# SOM.net
KiCad netlist of a schematic drawn in Altium Designer
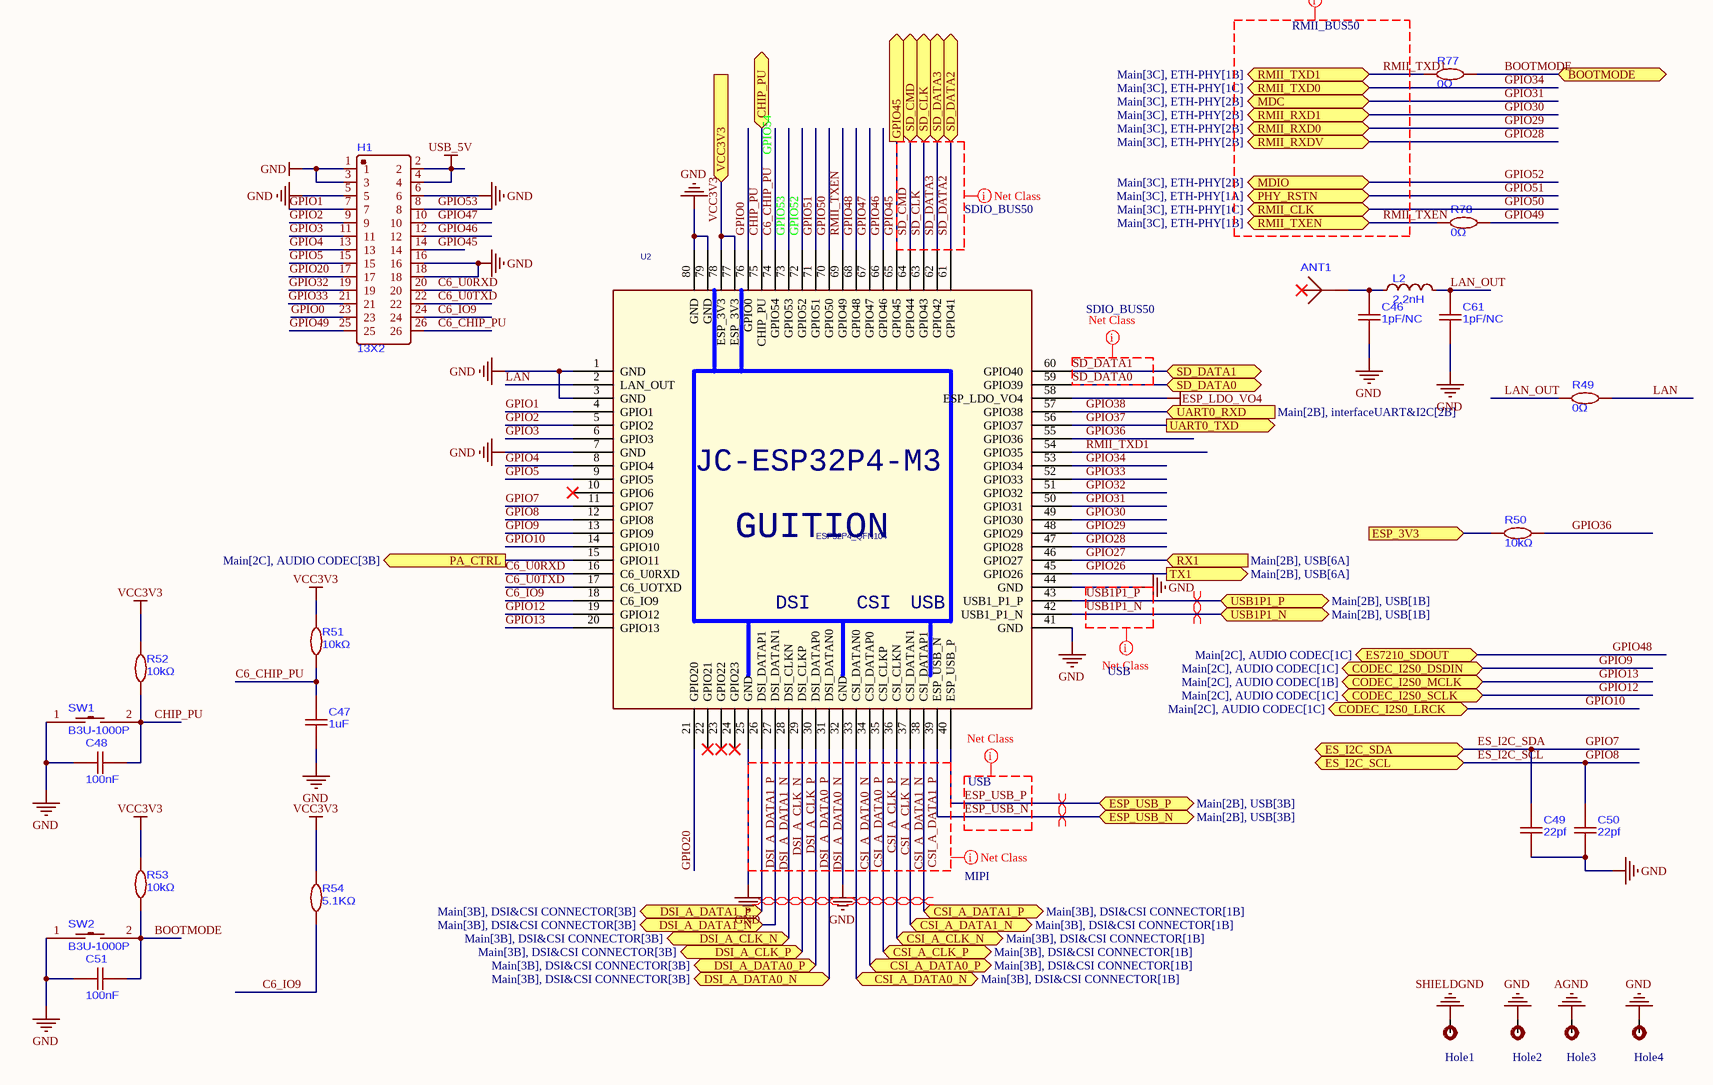
[diagram p0: SOM.SchDoc]

(export (version "E")
  (design (tool "Eeschema 10.0.6"))
  (components
    (comp (ref "ANT1")
      (value "RF ANT 2450MHz CERAMIC SMD")
      (footprint "ANT-SMD-2_L3.2-W1.6-C504002")
      (description "Ceramic Antenna 5.19dBi 100MHz 2.45GHz 1206 RF Antennas RoHS")
      (libsource (lib "Schlib2") (part "kinghelm KH-3216-A35"))
    )
    (comp (ref "C46")
      (value "1pF/NC")
      (footprint "C0402")
      (description "50V 1pF C0G 0603 Ceramic Capacitors RoHS")
      (libsource (lib "Schlib2") (part "FCC0603N1R0C500CT"))
    )
    (comp (ref "C47")
      (value "1uF")
      (footprint "C0603")
      (description "25V 1uF X7R ±10% 0603 Ceramic Capacitors ROHS")
      (libsource (lib "Schlib2") (part "CL10B105KA8NNNC"))
    )
    (comp (ref "C48")
      (value "100nF")
      (footprint "C0603")
      (description "50V 100nF X7R ±10% 0603 Ceramic Capacitors ROHS")
      (libsource (lib "Schlib2") (part "CC0603KRX7R9BB104"))
    )
    (comp (ref "C49")
      (value "22pf")
      (footprint "C0603")
      (description "50V 22pF C0G ±5% 0603 Ceramic Capacitors RoHS")
      (libsource (lib "Schlib2") (part "CL10C220JB8NNNC"))
    )
    (comp (ref "C50")
      (value "22pf")
      (footprint "C0603")
      (description "50V 22pF C0G ±5% 0603 Ceramic Capacitors RoHS")
      (libsource (lib "Schlib2") (part "CL10C220JB8NNNC"))
    )
    (comp (ref "C51")
      (value "100nF")
      (footprint "C0603")
      (description "50V 100nF X7R ±10% 0603 Ceramic Capacitors ROHS")
      (libsource (lib "Schlib2") (part "CC0603KRX7R9BB104"))
    )
    (comp (ref "C61")
      (value "1pF/NC")
      (footprint "C0402")
      (description "50V 1pF C0G 0603 Ceramic Capacitors RoHS")
      (libsource (lib "Schlib2") (part "FCC0603N1R0C500CT"))
    )
    (comp (ref "H1")
      (value "13X2")
      (footprint "HDR-TH_26P-P2.54-V-M-R2-C13-S2.54")
      (libsource (lib "Schlib2") (part "HX PZ2.54-2X13P ZZ"))
    )
    (comp (ref "Hole1")
      (value "Pad Big")
      (footprint "Screw 3.0")
      (libsource (lib "Schlib2") (part "Pad_Big"))
    )
    (comp (ref "Hole2")
      (value "Pad Big")
      (footprint "Screw 3.0")
      (libsource (lib "Schlib2") (part "Pad_Big"))
    )
    (comp (ref "Hole3")
      (value "Pad Big")
      (footprint "Screw 3.0")
      (libsource (lib "Schlib2") (part "Pad_Big"))
    )
    (comp (ref "Hole4")
      (value "Pad Big")
      (footprint "Screw 3.0")
      (libsource (lib "Schlib2") (part "Pad_Big"))
    )
    (comp (ref "L2")
      (value "2.2nH")
      (footprint "C0402")
      (description "700mA 2.2nH ±5% Wirewound Chip Inductor 80mΩ 0603 Fixed Inductors RoHS")
      (libsource (lib "Schlib2") (part "MQG06HF2N2JT7"))
    )
    (comp (ref "R49")
      (value "0Ω")
      (footprint "R0402")
      (description "100mW 0Ω 75V Thick Film Resistor ±5% 0603 Chip Resistor - Surface Mount RoHS")
      (libsource (lib "Schlib2") (part "RC0603JR-070RL"))
    )
    (comp (ref "R50")
      (value "10kΩ")
      (footprint "R0603")
      (description "100mW 10kΩ 75V ±100ppm/℃ Thick Film Resistor ±1% 0603 Chip Resistor - Surface Mount ROHS")
      (libsource (lib "Schlib2") (part "RC0603FR-0710KL"))
    )
    (comp (ref "R51")
      (value "10kΩ")
      (footprint "R0603")
      (description "100mW 10kΩ 75V ±100ppm/℃ Thick Film Resistor ±1% 0603 Chip Resistor - Surface Mount ROHS")
      (libsource (lib "Schlib2") (part "RC0603FR-0710KL"))
    )
    (comp (ref "R52")
      (value "10kΩ")
      (footprint "R0603")
      (description "100mW 10kΩ 75V ±100ppm/℃ Thick Film Resistor ±1% 0603 Chip Resistor - Surface Mount ROHS")
      (libsource (lib "Schlib2") (part "RC0603FR-0710KL"))
    )
    (comp (ref "R53")
      (value "10kΩ")
      (footprint "R0603")
      (description "100mW 10kΩ 75V ±100ppm/℃ Thick Film Resistor ±1% 0603 Chip Resistor - Surface Mount ROHS")
      (libsource (lib "Schlib2") (part "RC0603FR-0710KL"))
    )
    (comp (ref "R54")
      (value "5.1KΩ")
      (footprint "R0603")
      (description "100mW 5.1kΩ 75V ±100ppm/℃ Thick Film Resistor ±1% 0603 Chip Resistor - Surface Mount RoHS")
      (libsource (lib "Schlib2") (part "FRC0603F5101TS"))
    )
    (comp (ref "R77")
      (value "0Ω")
      (footprint "R0402")
      (description "100mW 0Ω 75V Thick Film Resistor ±5% 0603 Chip Resistor - Surface Mount RoHS")
      (libsource (lib "Schlib2") (part "RC0603JR-070RL"))
    )
    (comp (ref "R78")
      (value "0Ω")
      (footprint "R0402")
      (description "100mW 0Ω 75V Thick Film Resistor ±5% 0603 Chip Resistor - Surface Mount RoHS")
      (libsource (lib "Schlib2") (part "RC0603JR-070RL"))
    )
    (comp (ref "SW1")
      (value "B3U-1000P")
      (footprint "KEY-SMD_B3U-1000PM")
      (description "12V 2.5mm Round Button 3mm SPST 50mA SMD,3x2.5mm Tactile Switches ROHS")
      (libsource (lib "Schlib2") (part "B3U-1000P"))
    )
    (comp (ref "SW2")
      (value "B3U-1000P")
      (footprint "KEY-SMD_B3U-1000PM")
      (description "12V 2.5mm Round Button 3mm SPST 50mA SMD,3x2.5mm Tactile Switches ROHS")
      (libsource (lib "Schlib2") (part "B3U-1000P"))
    )
    (comp (ref "U2")
      (value "ESP32P4_QFN104")
      (footprint "JC-ESP32P4-M3_V0.2")
      (libsource (lib "Schlib2") (part "JC-ESP32P4-M3"))
    )
  )
  (nets
    (net (code "1") (name "/BOOTMODE") (class "Default")
      (node (ref "C51") (pin "1") (pinfunction "1_1") (pintype "passive"))
      (node (ref "R53") (pin "1") (pinfunction "1_1") (pintype "passive"))
      (node (ref "R77") (pin "2") (pinfunction "2_2") (pintype "passive"))
      (node (ref "SW2") (pin "2") (pinfunction "2_2") (pintype "passive"))
    )
    (net (code "2") (name "/C6_CHIP_PU") (class "Default")
      (node (ref "C47") (pin "2") (pinfunction "2_2") (pintype "passive"))
      (node (ref "H1") (pin "26") (pinfunction "26_26") (pintype "passive"))
      (node (ref "R51") (pin "1") (pinfunction "1_1") (pintype "passive"))
      (node (ref "U2") (pin "74") (pinfunction "GPIO54_74") (pintype "passive"))
    )
    (net (code "3") (name "/C6_IO9") (class "Default")
      (node (ref "H1") (pin "24") (pinfunction "24_24") (pintype "passive"))
      (node (ref "R54") (pin "1") (pinfunction "1_1") (pintype "passive"))
      (node (ref "U2") (pin "18") (pinfunction "C6_IO9_18") (pintype "passive"))
    )
    (net (code "4") (name "/C6_U0RXD") (class "Default")
      (node (ref "H1") (pin "20") (pinfunction "20_20") (pintype "passive"))
      (node (ref "U2") (pin "16") (pinfunction "C6_U0RXD_16") (pintype "passive"))
    )
    (net (code "5") (name "/C6_U0TXD") (class "Default")
      (node (ref "H1") (pin "22") (pinfunction "22_22") (pintype "passive"))
      (node (ref "U2") (pin "17") (pinfunction "C6_UOTXD_17") (pintype "passive"))
    )
    (net (code "6") (name "/CHIP_PU") (class "Default")
      (node (ref "C48") (pin "1") (pinfunction "1_1") (pintype "passive"))
      (node (ref "R52") (pin "1") (pinfunction "1_1") (pintype "passive"))
      (node (ref "SW1") (pin "2") (pinfunction "2_2") (pintype "passive"))
      (node (ref "U2") (pin "75") (pinfunction "CHIP_PU_75") (pintype "passive"))
    )
    (net (code "7") (name "/CSI_A_CLK_N") (class "Default")
      (node (ref "U2") (pin "36") (pinfunction "CSI_CLKN_36") (pintype "passive"))
    )
    (net (code "8") (name "/CSI_A_CLK_P") (class "Default")
      (node (ref "U2") (pin "35") (pinfunction "CSI_CLKP_35") (pintype "passive"))
    )
    (net (code "9") (name "/CSI_A_DATA0_N") (class "Default")
      (node (ref "U2") (pin "33") (pinfunction "CSI_DATAN0_33") (pintype "passive"))
    )
    (net (code "10") (name "/CSI_A_DATA0_P") (class "Default")
      (node (ref "U2") (pin "34") (pinfunction "CSI_DATAP0_34") (pintype "passive"))
    )
    (net (code "11") (name "/CSI_A_DATA1_N") (class "Default")
      (node (ref "U2") (pin "37") (pinfunction "CSI_DATAN1_37") (pintype "passive"))
    )
    (net (code "12") (name "/CSI_A_DATA1_P") (class "Default")
      (node (ref "U2") (pin "38") (pinfunction "CSI_DATAP1_38") (pintype "passive"))
    )
    (net (code "13") (name "/DSI_A_CLK_N") (class "Default")
      (node (ref "U2") (pin "28") (pinfunction "DSI_CLKN_28") (pintype "passive"))
    )
    (net (code "14") (name "/DSI_A_CLK_P") (class "Default")
      (node (ref "U2") (pin "29") (pinfunction "DSI_CLKP_29") (pintype "passive"))
    )
    (net (code "15") (name "/DSI_A_DATA0_N") (class "Default")
      (node (ref "U2") (pin "31") (pinfunction "DSI_DATAN0_31") (pintype "passive"))
    )
    (net (code "16") (name "/DSI_A_DATA0_P") (class "Default")
      (node (ref "U2") (pin "30") (pinfunction "DSI_DATAP0_30") (pintype "passive"))
    )
    (net (code "17") (name "/DSI_A_DATA1_N") (class "Default")
      (node (ref "U2") (pin "27") (pinfunction "DSI_DATAN1_27") (pintype "passive"))
    )
    (net (code "18") (name "/DSI_A_DATA1_P") (class "Default")
      (node (ref "U2") (pin "26") (pinfunction "DSI_DATAP1_26") (pintype "passive"))
    )
    (net (code "19") (name "/ESP_3V3") (class "Default")
      (node (ref "R50") (pin "1") (pinfunction "1_1") (pintype "passive"))
    )
    (net (code "20") (name "/ESP_USB_N") (class "Default")
      (node (ref "U2") (pin "39") (pinfunction "ESP_USB_N_39") (pintype "passive"))
    )
    (net (code "21") (name "/ESP_USB_P") (class "Default")
      (node (ref "U2") (pin "40") (pinfunction "ESP_USB_P_40") (pintype "passive"))
    )
    (net (code "22") (name "/ES_I2C_SCL") (class "Default")
      (node (ref "C50") (pin "2") (pinfunction "2_2") (pintype "passive"))
      (node (ref "U2") (pin "12") (pinfunction "GPIO8_12") (pintype "passive"))
    )
    (net (code "23") (name "/ES_I2C_SDA") (class "Default")
      (node (ref "C49") (pin "2") (pinfunction "2_2") (pintype "passive"))
      (node (ref "U2") (pin "11") (pinfunction "GPIO7_11") (pintype "passive"))
    )
    (net (code "24") (name "/GPIO0") (class "Default")
      (node (ref "H1") (pin "23") (pinfunction "23_23") (pintype "passive"))
      (node (ref "U2") (pin "76") (pinfunction "GPIO0_76") (pintype "passive"))
    )
    (net (code "25") (name "/GPIO1") (class "Default")
      (node (ref "H1") (pin "7") (pinfunction "7_7") (pintype "passive"))
      (node (ref "U2") (pin "4") (pinfunction "GPIO1_4") (pintype "passive"))
    )
    (net (code "26") (name "/GPIO2") (class "Default")
      (node (ref "H1") (pin "9") (pinfunction "9_9") (pintype "passive"))
      (node (ref "U2") (pin "5") (pinfunction "GPIO2_5") (pintype "passive"))
    )
    (net (code "27") (name "/GPIO3") (class "Default")
      (node (ref "H1") (pin "11") (pinfunction "11_11") (pintype "passive"))
      (node (ref "U2") (pin "6") (pinfunction "GPIO3_6") (pintype "passive"))
    )
    (net (code "28") (name "/GPIO4") (class "Default")
      (node (ref "H1") (pin "13") (pinfunction "13_13") (pintype "passive"))
      (node (ref "U2") (pin "8") (pinfunction "GPIO4_8") (pintype "passive"))
    )
    (net (code "29") (name "/GPIO5") (class "Default")
      (node (ref "H1") (pin "15") (pinfunction "15_15") (pintype "passive"))
      (node (ref "U2") (pin "9") (pinfunction "GPIO5_9") (pintype "passive"))
    )
    (net (code "30") (name "/GPIO9") (class "Default")
      (node (ref "U2") (pin "13") (pinfunction "GPIO9_13") (pintype "passive"))
    )
    (net (code "31") (name "/GPIO10") (class "Default")
      (node (ref "U2") (pin "14") (pinfunction "GPIO10_14") (pintype "passive"))
    )
    (net (code "32") (name "/GPIO12") (class "Default")
      (node (ref "U2") (pin "19") (pinfunction "GPIO12_19") (pintype "passive"))
    )
    (net (code "33") (name "/GPIO13") (class "Default")
      (node (ref "U2") (pin "20") (pinfunction "GPIO13_20") (pintype "passive"))
    )
    (net (code "34") (name "/GPIO20") (class "Default")
      (node (ref "H1") (pin "17") (pinfunction "17_17") (pintype "passive"))
      (node (ref "U2") (pin "21") (pinfunction "GPIO20_21") (pintype "passive"))
    )
    (net (code "35") (name "/GPIO26") (class "Default")
      (node (ref "U2") (pin "45") (pinfunction "GPIO26_45") (pintype "passive"))
    )
    (net (code "36") (name "/GPIO27") (class "Default")
      (node (ref "U2") (pin "46") (pinfunction "GPIO27_46") (pintype "passive"))
    )
    (net (code "37") (name "/GPIO28") (class "Default")
      (node (ref "U2") (pin "47") (pinfunction "GPIO28_47") (pintype "passive"))
    )
    (net (code "38") (name "/GPIO29") (class "Default")
      (node (ref "U2") (pin "48") (pinfunction "GPIO29_48") (pintype "passive"))
    )
    (net (code "39") (name "/GPIO30") (class "Default")
      (node (ref "U2") (pin "49") (pinfunction "GPIO30_49") (pintype "passive"))
    )
    (net (code "40") (name "/GPIO31") (class "Default")
      (node (ref "U2") (pin "50") (pinfunction "GPIO31_50") (pintype "passive"))
    )
    (net (code "41") (name "/GPIO32") (class "Default")
      (node (ref "H1") (pin "19") (pinfunction "19_19") (pintype "passive"))
      (node (ref "U2") (pin "51") (pinfunction "GPIO32_51") (pintype "passive"))
    )
    (net (code "42") (name "/GPIO33") (class "Default")
      (node (ref "H1") (pin "21") (pinfunction "21_21") (pintype "passive"))
      (node (ref "U2") (pin "52") (pinfunction "GPIO33_52") (pintype "passive"))
    )
    (net (code "43") (name "/GPIO34") (class "Default")
      (node (ref "U2") (pin "53") (pinfunction "GPIO34_53") (pintype "passive"))
    )
    (net (code "44") (name "/GPIO36") (class "Default")
      (node (ref "R50") (pin "2") (pinfunction "2_2") (pintype "passive"))
      (node (ref "U2") (pin "55") (pinfunction "GPIO36_55") (pintype "passive"))
    )
    (net (code "45") (name "/GPIO37") (class "Default")
      (node (ref "U2") (pin "56") (pinfunction "GPIO37_56") (pintype "passive"))
    )
    (net (code "46") (name "/GPIO38") (class "Default")
      (node (ref "U2") (pin "57") (pinfunction "GPIO38_57") (pintype "passive"))
    )
    (net (code "47") (name "/GPIO45") (class "Default")
      (node (ref "H1") (pin "14") (pinfunction "14_14") (pintype "passive"))
      (node (ref "U2") (pin "65") (pinfunction "GPIO45_65") (pintype "passive"))
    )
    (net (code "48") (name "/GPIO46") (class "Default")
      (node (ref "H1") (pin "12") (pinfunction "12_12") (pintype "passive"))
      (node (ref "U2") (pin "66") (pinfunction "GPIO46_66") (pintype "passive"))
    )
    (net (code "49") (name "/GPIO47") (class "Default")
      (node (ref "H1") (pin "10") (pinfunction "10_10") (pintype "passive"))
      (node (ref "U2") (pin "67") (pinfunction "GPIO47_67") (pintype "passive"))
    )
    (net (code "50") (name "/GPIO48") (class "Default")
      (node (ref "U2") (pin "68") (pinfunction "GPIO48_68") (pintype "passive"))
    )
    (net (code "51") (name "/GPIO49") (class "Default")
      (node (ref "H1") (pin "25") (pinfunction "25_25") (pintype "passive"))
      (node (ref "R78") (pin "2") (pinfunction "2_2") (pintype "passive"))
    )
    (net (code "52") (name "/GPIO50") (class "Default")
      (node (ref "U2") (pin "70") (pinfunction "GPIO50_70") (pintype "passive"))
    )
    (net (code "53") (name "/GPIO51") (class "Default")
      (node (ref "U2") (pin "71") (pinfunction "GPIO51_71") (pintype "passive"))
    )
    (net (code "54") (name "/GPIO52") (class "Default")
      (node (ref "U2") (pin "72") (pinfunction "GPIO52_72") (pintype "passive"))
    )
    (net (code "55") (name "/GPIO53") (class "Default")
      (node (ref "H1") (pin "8") (pinfunction "8_8") (pintype "passive"))
      (node (ref "U2") (pin "73") (pinfunction "GPIO53_73") (pintype "passive"))
    )
    (net (code "56") (name "/LAN") (class "Default")
      (node (ref "R49") (pin "2") (pinfunction "2_2") (pintype "passive"))
      (node (ref "U2") (pin "2") (pinfunction "LAN_OUT_2") (pintype "passive"))
    )
    (net (code "57") (name "/LAN_OUT") (class "Default")
      (node (ref "C61") (pin "2") (pinfunction "2_2") (pintype "passive"))
      (node (ref "L2") (pin "2") (pinfunction "2_2") (pintype "passive"))
      (node (ref "R49") (pin "1") (pinfunction "1_1") (pintype "passive"))
    )
    (net (code "58") (name "/PA_CTRL") (class "Default")
      (node (ref "U2") (pin "15") (pinfunction "GPIO11_15") (pintype "passive"))
    )
    (net (code "59") (name "/RMII_TXD1") (class "Default")
      (node (ref "R77") (pin "1") (pinfunction "1_1") (pintype "passive"))
      (node (ref "U2") (pin "54") (pinfunction "GPIO35_54") (pintype "passive"))
    )
    (net (code "60") (name "/RMII_TXEN") (class "Default")
      (node (ref "R78") (pin "1") (pinfunction "1_1") (pintype "passive"))
      (node (ref "U2") (pin "69") (pinfunction "GPIO49_69") (pintype "passive"))
    )
    (net (code "61") (name "/SD_CLK") (class "Default")
      (node (ref "U2") (pin "63") (pinfunction "GPIO43_63") (pintype "passive"))
    )
    (net (code "62") (name "/SD_CMD") (class "Default")
      (node (ref "U2") (pin "64") (pinfunction "GPIO44_64") (pintype "passive"))
    )
    (net (code "63") (name "/SD_DATA0") (class "Default")
      (node (ref "U2") (pin "59") (pinfunction "GPIO39_59") (pintype "passive"))
    )
    (net (code "64") (name "/SD_DATA1") (class "Default")
      (node (ref "U2") (pin "60") (pinfunction "GPIO40_60") (pintype "passive"))
    )
    (net (code "65") (name "/SD_DATA2") (class "Default")
      (node (ref "U2") (pin "61") (pinfunction "GPIO41_61") (pintype "passive"))
    )
    (net (code "66") (name "/SD_DATA3") (class "Default")
      (node (ref "U2") (pin "62") (pinfunction "GPIO42_62") (pintype "passive"))
    )
    (net (code "67") (name "/USB1P1_N") (class "Default")
      (node (ref "U2") (pin "42") (pinfunction "USB1_P1_N_42") (pintype "passive"))
    )
    (net (code "68") (name "/USB1P1_P") (class "Default")
      (node (ref "U2") (pin "43") (pinfunction "USB1_P1_P_43") (pintype "passive"))
    )
    (net (code "69") (name "AGND") (class "Default")
      (node (ref "Hole3") (pin "1") (pinfunction "1_1") (pintype "passive"))
    )
    (net (code "70") (name "ESP_LDO_VO4") (class "Default")
      (node (ref "U2") (pin "58") (pinfunction "ESP_LDO_VO4_58") (pintype "passive"))
    )
    (net (code "71") (name "GND") (class "Default")
      (node (ref "C46") (pin "1") (pinfunction "1_1") (pintype "passive"))
      (node (ref "C47") (pin "1") (pinfunction "1_1") (pintype "passive"))
      (node (ref "C48") (pin "2") (pinfunction "2_2") (pintype "passive"))
      (node (ref "C49") (pin "1") (pinfunction "1_1") (pintype "passive"))
      (node (ref "C50") (pin "1") (pinfunction "1_1") (pintype "passive"))
      (node (ref "C51") (pin "2") (pinfunction "2_2") (pintype "passive"))
      (node (ref "C61") (pin "1") (pinfunction "1_1") (pintype "passive"))
      (node (ref "H1") (pin "1") (pinfunction "1_1") (pintype "passive"))
      (node (ref "H1") (pin "16") (pinfunction "16_16") (pintype "passive"))
      (node (ref "H1") (pin "18") (pinfunction "18_18") (pintype "passive"))
      (node (ref "H1") (pin "3") (pinfunction "3_3") (pintype "passive"))
      (node (ref "H1") (pin "5") (pinfunction "5_5") (pintype "passive"))
      (node (ref "H1") (pin "6") (pinfunction "6_6") (pintype "passive"))
      (node (ref "Hole2") (pin "1") (pinfunction "1_1") (pintype "passive"))
      (node (ref "Hole4") (pin "1") (pinfunction "1_1") (pintype "passive"))
      (node (ref "SW1") (pin "1") (pinfunction "1_1") (pintype "passive"))
      (node (ref "SW2") (pin "1") (pinfunction "1_1") (pintype "passive"))
      (node (ref "U2") (pin "1") (pinfunction "GND_1") (pintype "passive"))
      (node (ref "U2") (pin "25") (pinfunction "GND_25") (pintype "passive"))
      (node (ref "U2") (pin "3") (pinfunction "GND_3") (pintype "passive"))
      (node (ref "U2") (pin "32") (pinfunction "GND_32") (pintype "passive"))
      (node (ref "U2") (pin "41") (pinfunction "GND_41") (pintype "passive"))
      (node (ref "U2") (pin "44") (pinfunction "GND_44") (pintype "passive"))
      (node (ref "U2") (pin "7") (pinfunction "GND_7") (pintype "passive"))
      (node (ref "U2") (pin "79") (pinfunction "GND_79") (pintype "passive"))
      (node (ref "U2") (pin "80") (pinfunction "GND_80") (pintype "passive"))
    )
    (net (code "72") (name "Net-(ANT1-Pad2)") (class "Default")
      (node (ref "ANT1") (pin "2") (pinfunction "2_2") (pintype "passive"))
      (node (ref "C46") (pin "2") (pinfunction "2_2") (pintype "passive"))
      (node (ref "L2") (pin "1") (pinfunction "1_1") (pintype "passive"))
    )
    (net (code "73") (name "SHIELDGND") (class "Default")
      (node (ref "Hole1") (pin "1") (pinfunction "1_1") (pintype "passive"))
    )
    (net (code "74") (name "USB_5V") (class "Default")
      (node (ref "H1") (pin "2") (pinfunction "2_2") (pintype "passive"))
      (node (ref "H1") (pin "4") (pinfunction "4_4") (pintype "passive"))
    )
    (net (code "75") (name "VCC3V3") (class "Default")
      (node (ref "R51") (pin "2") (pinfunction "2_2") (pintype "passive"))
      (node (ref "R52") (pin "2") (pinfunction "2_2") (pintype "passive"))
      (node (ref "R53") (pin "2") (pinfunction "2_2") (pintype "passive"))
      (node (ref "R54") (pin "2") (pinfunction "2_2") (pintype "passive"))
      (node (ref "U2") (pin "77") (pinfunction "ESP_3V3_77") (pintype "passive"))
      (node (ref "U2") (pin "78") (pinfunction "ESP_3V3_78") (pintype "passive"))
    )
    (net (code "76") (name "unconnected-(ANT1-ANT-Pad1)") (class "Default")
      (node (ref "ANT1") (pin "1") (pinfunction "ANT_1") (pintype "passive+no_connect"))
    )
    (net (code "77") (name "unconnected-(U2-GPIO6-Pad10)") (class "Default")
      (node (ref "U2") (pin "10") (pinfunction "GPIO6_10") (pintype "passive+no_connect"))
    )
    (net (code "78") (name "unconnected-(U2-GPIO21-Pad22)") (class "Default")
      (node (ref "U2") (pin "22") (pinfunction "GPIO21_22") (pintype "passive+no_connect"))
    )
    (net (code "79") (name "unconnected-(U2-GPIO22-Pad23)") (class "Default")
      (node (ref "U2") (pin "23") (pinfunction "GPIO22_23") (pintype "passive+no_connect"))
    )
    (net (code "80") (name "unconnected-(U2-GPIO23-Pad24)") (class "Default")
      (node (ref "U2") (pin "24") (pinfunction "GPIO23_24") (pintype "passive+no_connect"))
    )
  )
)
